# sheet_V1.net
KiCad netlist of a schematic drawn in Altium Designer
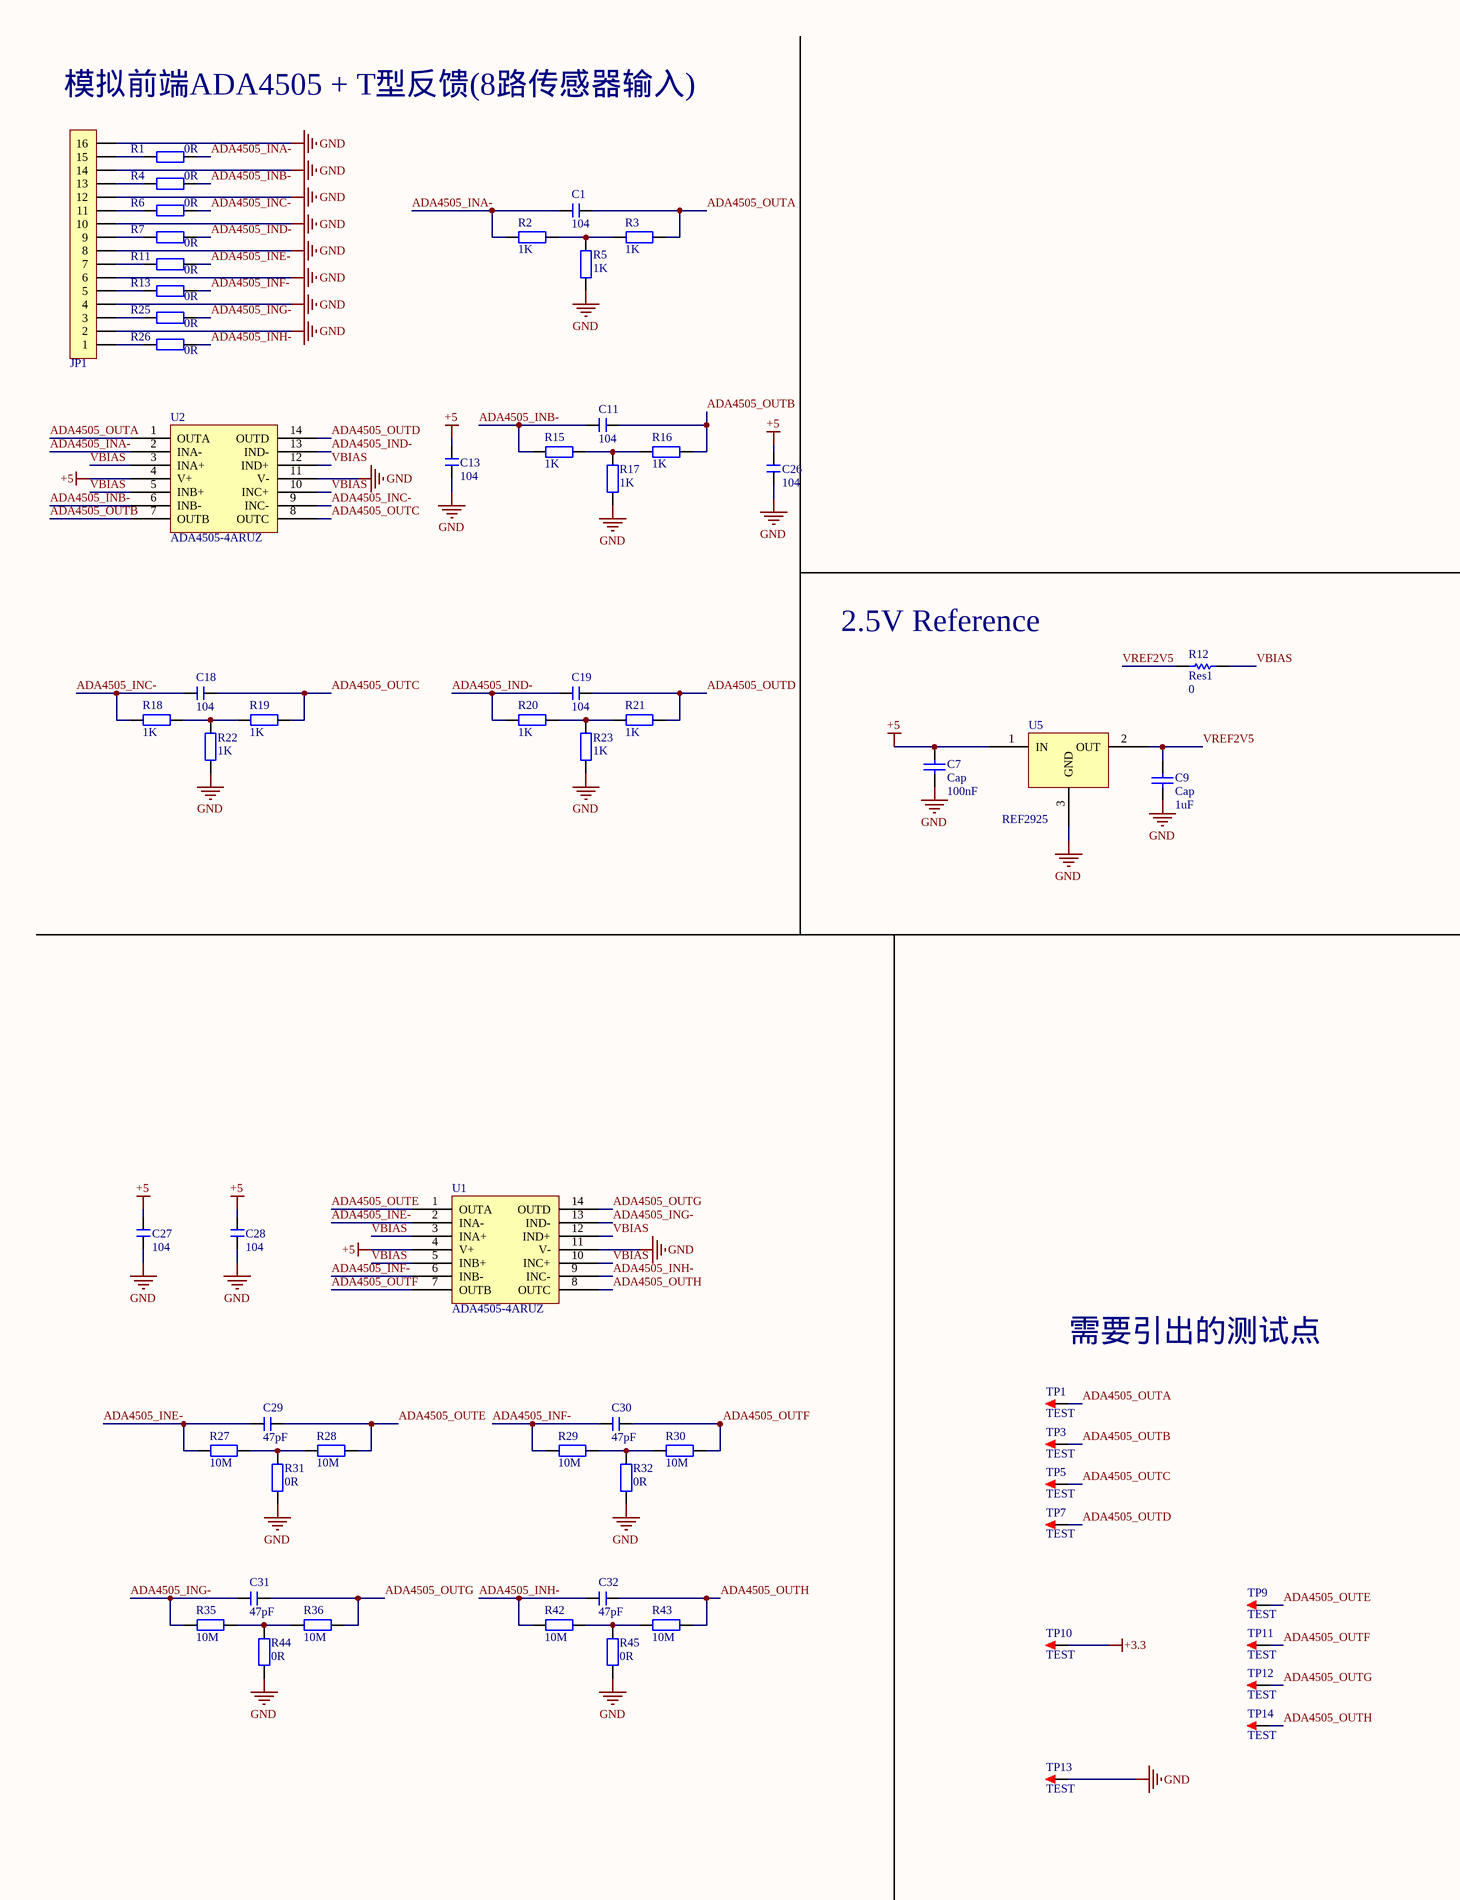
[diagram p0: sheet_V1.SchDoc, left]
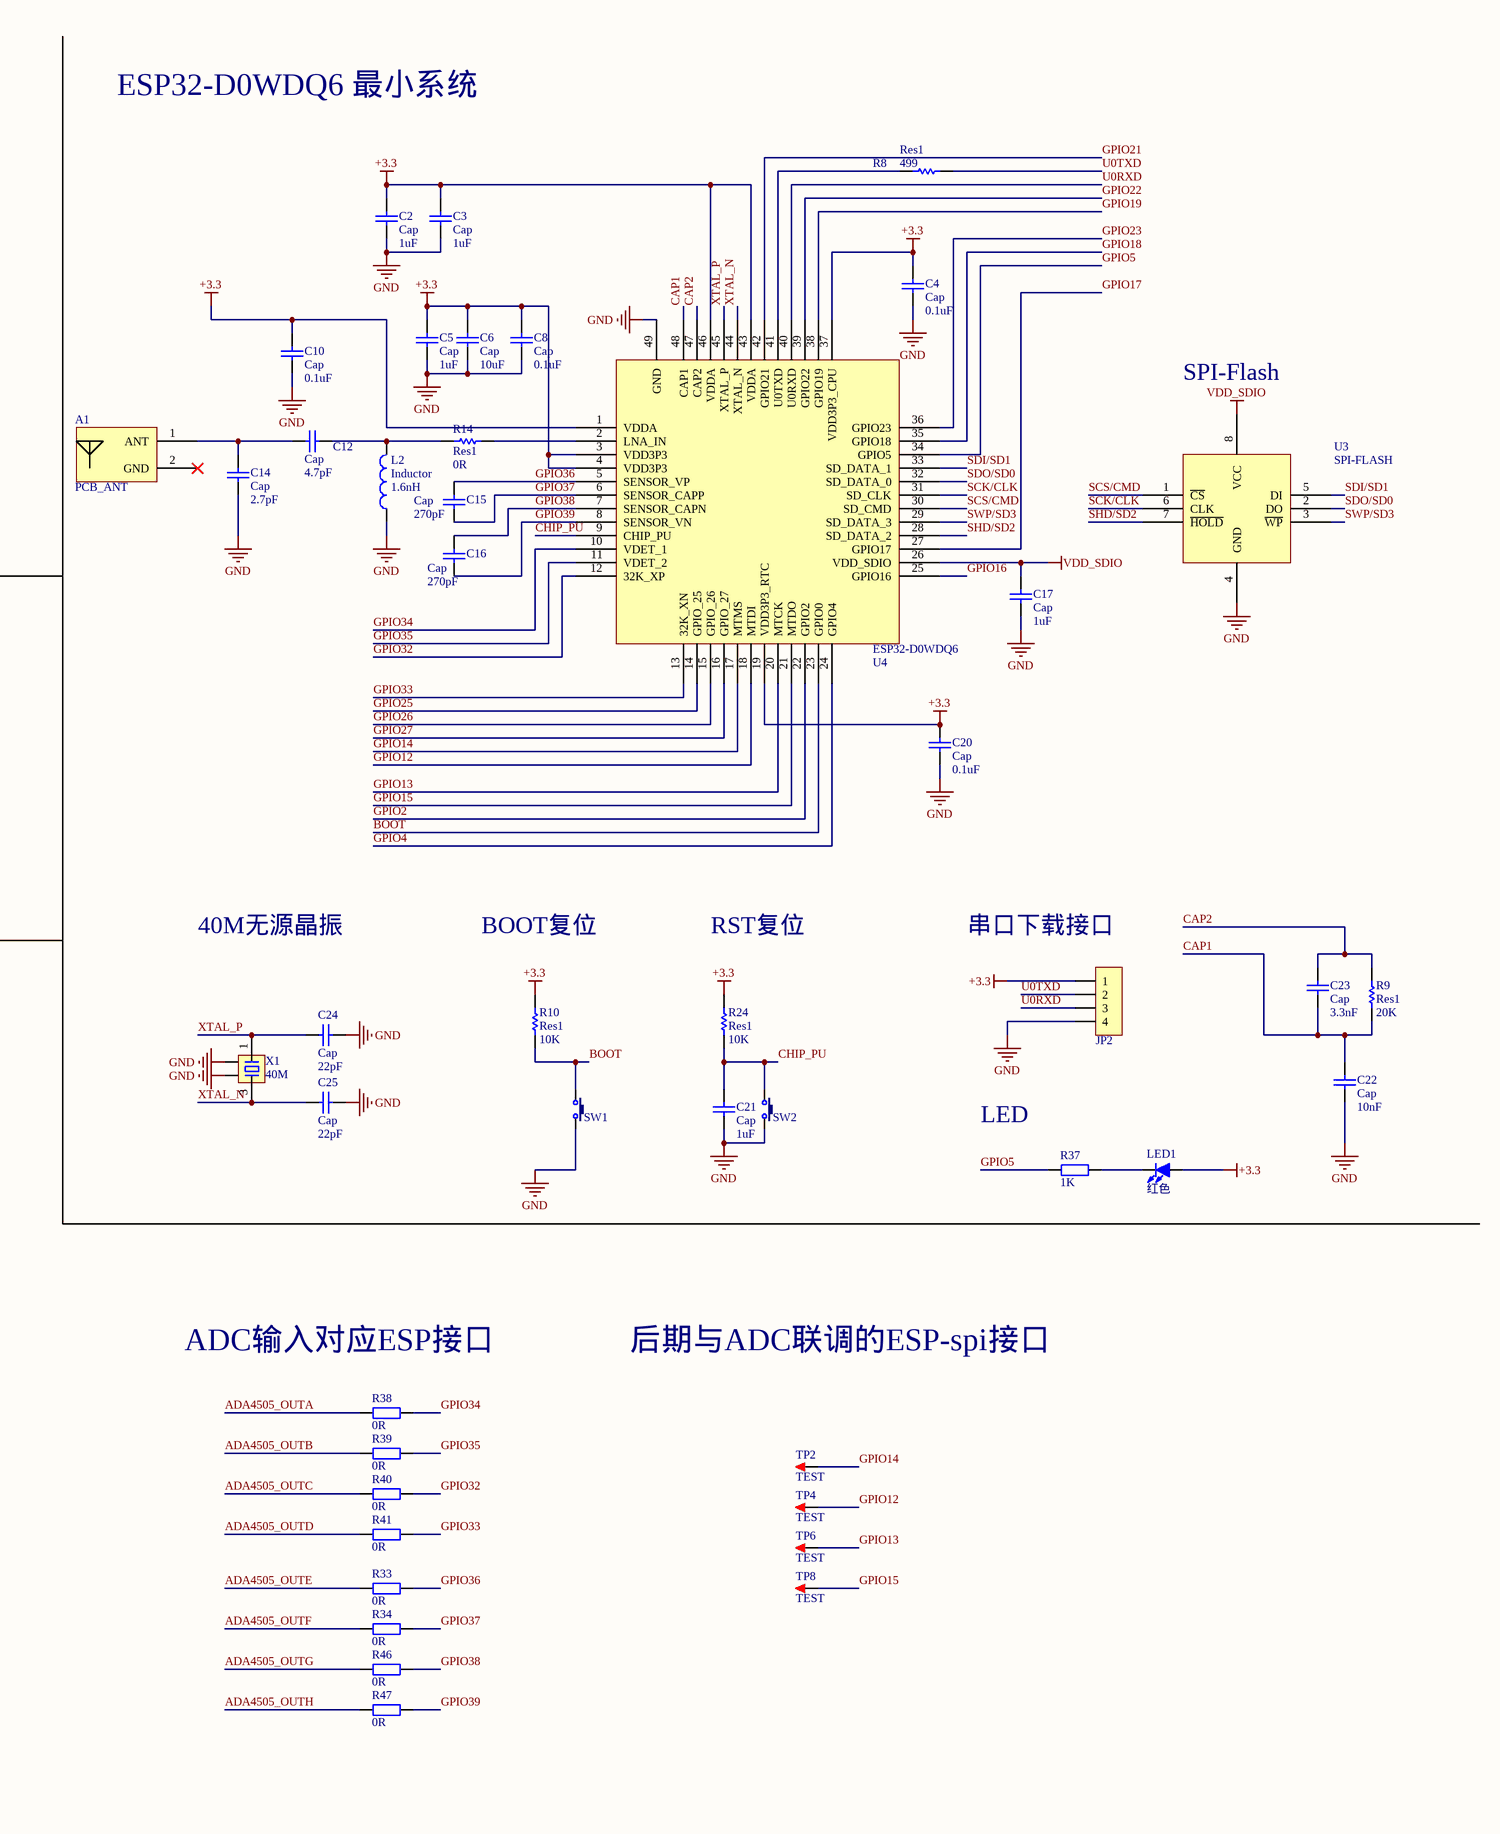
[diagram p1: sheet_V1.SchDoc, right]

(export (version "E")
  (design (tool "Eeschema 10.0.6"))
  (components
    (comp (ref "A1")
      (value "PCB_ANT")
      (footprint "PCB_ANT")
      (description "2.4G-esp32")
      (libsource (lib "Schlib1") (part "PCB_ANT"))
    )
    (comp (ref "C1")
      (value "104")
      (footprint "C 0402_L")
      (description "无极性贴片电容")
      (fields (field (name "版权归属") "源创客"))
      (libsource (lib "Basic_Integrated_Library") (part "C"))
    )
    (comp (ref "C2")
      (value "Cap")
      (footprint "C 0402_L")
      (description "Capacitor")
      (fields (field (name "ALTIUM_VALUE") "1uF") (field (name "PUBLISHER") "Altium Limited"))
      (libsource (lib "Miscellaneous Devices") (part "Cap"))
    )
    (comp (ref "C3")
      (value "Cap")
      (footprint "C 0402_L")
      (description "Capacitor")
      (fields (field (name "ALTIUM_VALUE") "1uF") (field (name "PUBLISHER") "Altium Limited"))
      (libsource (lib "Miscellaneous Devices") (part "Cap"))
    )
    (comp (ref "C4")
      (value "Cap")
      (footprint "C 0402_L")
      (description "Capacitor")
      (fields (field (name "ALTIUM_VALUE") "0.1uF") (field (name "PUBLISHER") "Altium Limited"))
      (libsource (lib "Miscellaneous Devices") (part "Cap"))
    )
    (comp (ref "C5")
      (value "Cap")
      (footprint "C 0402_L")
      (description "Capacitor")
      (fields (field (name "ALTIUM_VALUE") "1uF") (field (name "PUBLISHER") "Altium Limited"))
      (libsource (lib "Miscellaneous Devices") (part "Cap"))
    )
    (comp (ref "C6")
      (value "Cap")
      (footprint "C 0402_L")
      (description "Capacitor")
      (fields (field (name "ALTIUM_VALUE") "10uF") (field (name "PUBLISHER") "Altium Limited"))
      (libsource (lib "Miscellaneous Devices") (part "Cap"))
    )
    (comp (ref "C7")
      (value "Cap")
      (footprint "C 0402_L")
      (description "Capacitor")
      (fields (field (name "ALTIUM_VALUE") "100nF") (field (name "PUBLISHER") "Altium Limited"))
      (libsource (lib "Miscellaneous Devices") (part "Cap"))
    )
    (comp (ref "C8")
      (value "Cap")
      (footprint "C 0402_L")
      (description "Capacitor")
      (fields (field (name "ALTIUM_VALUE") "0.1uF") (field (name "PUBLISHER") "Altium Limited"))
      (libsource (lib "Miscellaneous Devices") (part "Cap"))
    )
    (comp (ref "C9")
      (value "Cap")
      (footprint "C 0402_L")
      (description "Capacitor")
      (fields (field (name "ALTIUM_VALUE") "1uF") (field (name "PUBLISHER") "Altium Limited"))
      (libsource (lib "Miscellaneous Devices") (part "Cap"))
    )
    (comp (ref "C10")
      (value "Cap")
      (footprint "C 0402_L")
      (description "Capacitor")
      (fields (field (name "ALTIUM_VALUE") "0.1uF") (field (name "PUBLISHER") "Altium Limited"))
      (libsource (lib "Miscellaneous Devices") (part "Cap"))
    )
    (comp (ref "C11")
      (value "104")
      (footprint "C 0402_L")
      (description "无极性贴片电容")
      (fields (field (name "版权归属") "源创客"))
      (libsource (lib "Basic_Integrated_Library") (part "C"))
    )
    (comp (ref "C12")
      (value "Cap")
      (footprint "C 0402_L")
      (description "Capacitor")
      (fields (field (name "ALTIUM_VALUE") "4.7pF") (field (name "PUBLISHER") "Altium Limited"))
      (libsource (lib "Miscellaneous Devices") (part "Cap"))
    )
    (comp (ref "C13")
      (value "104")
      (footprint "C 0402_L")
      (description "无极性贴片电容")
      (fields (field (name "版权归属") "源创客"))
      (libsource (lib "Basic_Integrated_Library") (part "C"))
    )
    (comp (ref "C14")
      (value "Cap")
      (footprint "C 0402_L")
      (description "Capacitor")
      (fields (field (name "ALTIUM_VALUE") "2.7pF") (field (name "PUBLISHER") "Altium Limited"))
      (libsource (lib "Miscellaneous Devices") (part "Cap"))
    )
    (comp (ref "C15")
      (value "Cap")
      (footprint "C 0402_L")
      (description "Capacitor")
      (fields (field (name "ALTIUM_VALUE") "270pF") (field (name "PUBLISHER") "Altium Limited"))
      (libsource (lib "Miscellaneous Devices") (part "Cap"))
    )
    (comp (ref "C16")
      (value "Cap")
      (footprint "C 0402_L")
      (description "Capacitor")
      (fields (field (name "ALTIUM_VALUE") "270pF") (field (name "PUBLISHER") "Altium Limited"))
      (libsource (lib "Miscellaneous Devices") (part "Cap"))
    )
    (comp (ref "C17")
      (value "Cap")
      (footprint "C 0402_L")
      (description "Capacitor")
      (fields (field (name "ALTIUM_VALUE") "1uF") (field (name "PUBLISHER") "Altium Limited"))
      (libsource (lib "Miscellaneous Devices") (part "Cap"))
    )
    (comp (ref "C18")
      (value "104")
      (footprint "C 0402_L")
      (description "无极性贴片电容")
      (fields (field (name "版权归属") "源创客"))
      (libsource (lib "Basic_Integrated_Library") (part "C"))
    )
    (comp (ref "C19")
      (value "104")
      (footprint "C 0402_L")
      (description "无极性贴片电容")
      (fields (field (name "版权归属") "源创客"))
      (libsource (lib "Basic_Integrated_Library") (part "C"))
    )
    (comp (ref "C20")
      (value "Cap")
      (footprint "C 0402_L")
      (description "Capacitor")
      (fields (field (name "ALTIUM_VALUE") "0.1uF") (field (name "PUBLISHER") "Altium Limited"))
      (libsource (lib "Miscellaneous Devices") (part "Cap"))
    )
    (comp (ref "C21")
      (value "Cap")
      (footprint "C 0402_L")
      (description "Capacitor")
      (fields (field (name "ALTIUM_VALUE") "1uF") (field (name "PUBLISHER") "Altium Limited"))
      (libsource (lib "Miscellaneous Devices") (part "Cap"))
    )
    (comp (ref "C22")
      (value "Cap")
      (footprint "C 0402_L")
      (description "Capacitor")
      (fields (field (name "ALTIUM_VALUE") "10nF") (field (name "PUBLISHER") "Altium Limited"))
      (libsource (lib "Miscellaneous Devices") (part "Cap"))
    )
    (comp (ref "C23")
      (value "Cap")
      (footprint "C 0402_L")
      (description "Capacitor")
      (fields (field (name "ALTIUM_VALUE") "3.3nF") (field (name "PUBLISHER") "Altium Limited"))
      (libsource (lib "Miscellaneous Devices") (part "Cap"))
    )
    (comp (ref "C24")
      (value "Cap")
      (footprint "C 0402_L")
      (description "Capacitor")
      (fields (field (name "ALTIUM_VALUE") "22pF") (field (name "PUBLISHER") "Altium Limited"))
      (libsource (lib "Miscellaneous Devices") (part "Cap"))
    )
    (comp (ref "C25")
      (value "Cap")
      (footprint "C 0402_L")
      (description "Capacitor")
      (fields (field (name "ALTIUM_VALUE") "22pF") (field (name "PUBLISHER") "Altium Limited"))
      (libsource (lib "Miscellaneous Devices") (part "Cap"))
    )
    (comp (ref "C26")
      (value "104")
      (footprint "C 0402_L")
      (description "无极性贴片电容")
      (fields (field (name "版权归属") "源创客"))
      (libsource (lib "Basic_Integrated_Library") (part "C"))
    )
    (comp (ref "C27")
      (value "104")
      (footprint "C 0402_L")
      (description "无极性贴片电容")
      (fields (field (name "版权归属") "源创客"))
      (libsource (lib "Basic_Integrated_Library") (part "C"))
    )
    (comp (ref "C28")
      (value "104")
      (footprint "C 0402_L")
      (description "无极性贴片电容")
      (fields (field (name "版权归属") "源创客"))
      (libsource (lib "Basic_Integrated_Library") (part "C"))
    )
    (comp (ref "C29")
      (value "47pF")
      (footprint "C 0402_L")
      (description "无极性贴片电容")
      (fields (field (name "版权归属") "源创客"))
      (libsource (lib "Basic_Integrated_Library") (part "C"))
    )
    (comp (ref "C30")
      (value "47pF")
      (footprint "C 0402_L")
      (description "无极性贴片电容")
      (fields (field (name "版权归属") "源创客"))
      (libsource (lib "Basic_Integrated_Library") (part "C"))
    )
    (comp (ref "C31")
      (value "47pF")
      (footprint "C 0402_L")
      (description "无极性贴片电容")
      (fields (field (name "版权归属") "源创客"))
      (libsource (lib "Basic_Integrated_Library") (part "C"))
    )
    (comp (ref "C32")
      (value "47pF")
      (footprint "C 0402_L")
      (description "无极性贴片电容")
      (fields (field (name "版权归属") "源创客"))
      (libsource (lib "Basic_Integrated_Library") (part "C"))
    )
    (comp (ref "JP1")
      (value "HDR-1X16")
      (footprint "FPC0.5 2H-WS-16P")
      (description "16P接插件")
      (fields (field (name "版权归属") "源创客"))
      (libsource (lib "Basic_Integrated_Library") (part "Header 16"))
    )
    (comp (ref "JP2")
      (value "HDR-1X4")
      (footprint "2.54_pad_4")
      (description "4P接插件")
      (fields (field (name "版权归属") "源创客"))
      (libsource (lib "Basic_Integrated_Library") (part "Header 4"))
    )
    (comp (ref "L2")
      (value "Inductor")
      (footprint "L 0402")
      (fields (field (name "ALTIUM_VALUE") "1.6nH") (field (name "PUBLISHER") "Altium Limited"))
      (libsource (lib "Miscellaneous Devices") (part "Inductor"))
    )
    (comp (ref "LED1")
      (value "红色")
      (footprint "LED 0603R")
      (description "贴片LED")
      (fields (field (name "版权归属") "源创客"))
      (libsource (lib "Basic_Integrated_Library") (part "LED-SMD"))
    )
    (comp (ref "R1")
      (value "0R")
      (footprint "R 0402_L")
      (description "贴片电阻")
      (fields (field (name "版权归属") "源创客"))
      (libsource (lib "Basic_Integrated_Library") (part "R"))
    )
    (comp (ref "R2")
      (value "1K")
      (footprint "R 0805_L")
      (description "贴片电阻")
      (fields (field (name "版权归属") "源创客"))
      (libsource (lib "Basic_Integrated_Library") (part "R"))
    )
    (comp (ref "R3")
      (value "1K")
      (footprint "R 0805_L")
      (description "贴片电阻")
      (fields (field (name "版权归属") "源创客"))
      (libsource (lib "Basic_Integrated_Library") (part "R"))
    )
    (comp (ref "R4")
      (value "0R")
      (footprint "R 0402_L")
      (description "贴片电阻")
      (fields (field (name "版权归属") "源创客"))
      (libsource (lib "Basic_Integrated_Library") (part "R"))
    )
    (comp (ref "R5")
      (value "1K")
      (footprint "R 0805_L")
      (description "贴片电阻")
      (fields (field (name "版权归属") "源创客"))
      (libsource (lib "Basic_Integrated_Library") (part "R"))
    )
    (comp (ref "R6")
      (value "0R")
      (footprint "R 0402_L")
      (description "贴片电阻")
      (fields (field (name "版权归属") "源创客"))
      (libsource (lib "Basic_Integrated_Library") (part "R"))
    )
    (comp (ref "R7")
      (value "0R")
      (footprint "R 0402_L")
      (description "贴片电阻")
      (fields (field (name "版权归属") "源创客"))
      (libsource (lib "Basic_Integrated_Library") (part "R"))
    )
    (comp (ref "R8")
      (value "Res1")
      (footprint "R 0402_L")
      (description "Resistor")
      (fields (field (name "ALTIUM_VALUE") "499") (field (name "PUBLISHER") "Altium Limited"))
      (libsource (lib "Miscellaneous Devices") (part "Res1"))
    )
    (comp (ref "R9")
      (value "Res1")
      (footprint "R 0402_L")
      (description "Resistor")
      (fields (field (name "ALTIUM_VALUE") "20K") (field (name "PUBLISHER") "Altium Limited"))
      (libsource (lib "Miscellaneous Devices") (part "Res1"))
    )
    (comp (ref "R10")
      (value "Res1")
      (footprint "R 0402_L")
      (description "Resistor")
      (fields (field (name "ALTIUM_VALUE") "10K") (field (name "PUBLISHER") "Altium Limited"))
      (libsource (lib "Miscellaneous Devices") (part "Res1"))
    )
    (comp (ref "R11")
      (value "0R")
      (footprint "R 0402_L")
      (description "贴片电阻")
      (fields (field (name "版权归属") "源创客"))
      (libsource (lib "Basic_Integrated_Library") (part "R"))
    )
    (comp (ref "R12")
      (value "Res1")
      (footprint "R 0402_L")
      (description "Resistor")
      (fields (field (name "ALTIUM_VALUE") "0") (field (name "PUBLISHER") "Altium Limited"))
      (libsource (lib "Miscellaneous Devices") (part "Res1"))
    )
    (comp (ref "R13")
      (value "0R")
      (footprint "R 0402_L")
      (description "贴片电阻")
      (fields (field (name "版权归属") "源创客"))
      (libsource (lib "Basic_Integrated_Library") (part "R"))
    )
    (comp (ref "R14")
      (value "Res1")
      (footprint "R 0402_L")
      (description "Resistor")
      (fields (field (name "ALTIUM_VALUE") "0R") (field (name "PUBLISHER") "Altium Limited"))
      (libsource (lib "Miscellaneous Devices") (part "Res1"))
    )
    (comp (ref "R15")
      (value "1K")
      (footprint "R 0805_L")
      (description "贴片电阻")
      (fields (field (name "版权归属") "源创客"))
      (libsource (lib "Basic_Integrated_Library") (part "R"))
    )
    (comp (ref "R16")
      (value "1K")
      (footprint "R 0805_L")
      (description "贴片电阻")
      (fields (field (name "版权归属") "源创客"))
      (libsource (lib "Basic_Integrated_Library") (part "R"))
    )
    (comp (ref "R17")
      (value "1K")
      (footprint "R 0805_L")
      (description "贴片电阻")
      (fields (field (name "版权归属") "源创客"))
      (libsource (lib "Basic_Integrated_Library") (part "R"))
    )
    (comp (ref "R18")
      (value "1K")
      (footprint "R 0805_L")
      (description "贴片电阻")
      (fields (field (name "版权归属") "源创客"))
      (libsource (lib "Basic_Integrated_Library") (part "R"))
    )
    (comp (ref "R19")
      (value "1K")
      (footprint "R 0805_L")
      (description "贴片电阻")
      (fields (field (name "版权归属") "源创客"))
      (libsource (lib "Basic_Integrated_Library") (part "R"))
    )
    (comp (ref "R20")
      (value "1K")
      (footprint "R 0805_L")
      (description "贴片电阻")
      (fields (field (name "版权归属") "源创客"))
      (libsource (lib "Basic_Integrated_Library") (part "R"))
    )
    (comp (ref "R21")
      (value "1K")
      (footprint "R 0805_L")
      (description "贴片电阻")
      (fields (field (name "版权归属") "源创客"))
      (libsource (lib "Basic_Integrated_Library") (part "R"))
    )
    (comp (ref "R22")
      (value "1K")
      (footprint "R 0805_L")
      (description "贴片电阻")
      (fields (field (name "版权归属") "源创客"))
      (libsource (lib "Basic_Integrated_Library") (part "R"))
    )
    (comp (ref "R23")
      (value "1K")
      (footprint "R 0805_L")
      (description "贴片电阻")
      (fields (field (name "版权归属") "源创客"))
      (libsource (lib "Basic_Integrated_Library") (part "R"))
    )
    (comp (ref "R24")
      (value "Res1")
      (footprint "R 0402_L")
      (description "Resistor")
      (fields (field (name "ALTIUM_VALUE") "10K") (field (name "PUBLISHER") "Altium Limited"))
      (libsource (lib "Miscellaneous Devices") (part "Res1"))
    )
    (comp (ref "R25")
      (value "0R")
      (footprint "R 0402_L")
      (description "贴片电阻")
      (fields (field (name "版权归属") "源创客"))
      (libsource (lib "Basic_Integrated_Library") (part "R"))
    )
    (comp (ref "R26")
      (value "0R")
      (footprint "R 0402_L")
      (description "贴片电阻")
      (fields (field (name "版权归属") "源创客"))
      (libsource (lib "Basic_Integrated_Library") (part "R"))
    )
    (comp (ref "R27")
      (value "10M")
      (footprint "R 0805_L")
      (description "贴片电阻")
      (fields (field (name "版权归属") "源创客"))
      (libsource (lib "Basic_Integrated_Library") (part "R"))
    )
    (comp (ref "R28")
      (value "10M")
      (footprint "R 0805_L")
      (description "贴片电阻")
      (fields (field (name "版权归属") "源创客"))
      (libsource (lib "Basic_Integrated_Library") (part "R"))
    )
    (comp (ref "R29")
      (value "10M")
      (footprint "R 0805_L")
      (description "贴片电阻")
      (fields (field (name "版权归属") "源创客"))
      (libsource (lib "Basic_Integrated_Library") (part "R"))
    )
    (comp (ref "R30")
      (value "10M")
      (footprint "R 0805_L")
      (description "贴片电阻")
      (fields (field (name "版权归属") "源创客"))
      (libsource (lib "Basic_Integrated_Library") (part "R"))
    )
    (comp (ref "R31")
      (value "0R")
      (footprint "R 0805_L")
      (description "贴片电阻")
      (fields (field (name "版权归属") "源创客"))
      (libsource (lib "Basic_Integrated_Library") (part "R"))
    )
    (comp (ref "R32")
      (value "0R")
      (footprint "R 0805_L")
      (description "贴片电阻")
      (fields (field (name "版权归属") "源创客"))
      (libsource (lib "Basic_Integrated_Library") (part "R"))
    )
    (comp (ref "R33")
      (value "0R")
      (footprint "R 0402_L")
      (description "贴片电阻")
      (fields (field (name "版权归属") "源创客"))
      (libsource (lib "Basic_Integrated_Library") (part "R"))
    )
    (comp (ref "R34")
      (value "0R")
      (footprint "R 0402_L")
      (description "贴片电阻")
      (fields (field (name "版权归属") "源创客"))
      (libsource (lib "Basic_Integrated_Library") (part "R"))
    )
    (comp (ref "R35")
      (value "10M")
      (footprint "R 0805_L")
      (description "贴片电阻")
      (fields (field (name "版权归属") "源创客"))
      (libsource (lib "Basic_Integrated_Library") (part "R"))
    )
    (comp (ref "R36")
      (value "10M")
      (footprint "R 0805_L")
      (description "贴片电阻")
      (fields (field (name "版权归属") "源创客"))
      (libsource (lib "Basic_Integrated_Library") (part "R"))
    )
    (comp (ref "R37")
      (value "1K")
      (footprint "R 0402_L")
      (description "贴片电阻")
      (fields (field (name "版权归属") "源创客"))
      (libsource (lib "Basic_Integrated_Library") (part "R"))
    )
    (comp (ref "R38")
      (value "0R")
      (footprint "R 0402_L")
      (description "贴片电阻")
      (fields (field (name "版权归属") "源创客"))
      (libsource (lib "Basic_Integrated_Library") (part "R"))
    )
    (comp (ref "R39")
      (value "0R")
      (footprint "R 0402_L")
      (description "贴片电阻")
      (fields (field (name "版权归属") "源创客"))
      (libsource (lib "Basic_Integrated_Library") (part "R"))
    )
    (comp (ref "R40")
      (value "0R")
      (footprint "R 0402_L")
      (description "贴片电阻")
      (fields (field (name "版权归属") "源创客"))
      (libsource (lib "Basic_Integrated_Library") (part "R"))
    )
    (comp (ref "R41")
      (value "0R")
      (footprint "R 0402_L")
      (description "贴片电阻")
      (fields (field (name "版权归属") "源创客"))
      (libsource (lib "Basic_Integrated_Library") (part "R"))
    )
    (comp (ref "R42")
      (value "10M")
      (footprint "R 0805_L")
      (description "贴片电阻")
      (fields (field (name "版权归属") "源创客"))
      (libsource (lib "Basic_Integrated_Library") (part "R"))
    )
    (comp (ref "R43")
      (value "10M")
      (footprint "R 0805_L")
      (description "贴片电阻")
      (fields (field (name "版权归属") "源创客"))
      (libsource (lib "Basic_Integrated_Library") (part "R"))
    )
    (comp (ref "R44")
      (value "0R")
      (footprint "R 0805_L")
      (description "贴片电阻")
      (fields (field (name "版权归属") "源创客"))
      (libsource (lib "Basic_Integrated_Library") (part "R"))
    )
    (comp (ref "R45")
      (value "0R")
      (footprint "R 0805_L")
      (description "贴片电阻")
      (fields (field (name "版权归属") "源创客"))
      (libsource (lib "Basic_Integrated_Library") (part "R"))
    )
    (comp (ref "R46")
      (value "0R")
      (footprint "R 0402_L")
      (description "贴片电阻")
      (fields (field (name "版权归属") "源创客"))
      (libsource (lib "Basic_Integrated_Library") (part "R"))
    )
    (comp (ref "R47")
      (value "0R")
      (footprint "R 0402_L")
      (description "贴片电阻")
      (fields (field (name "版权归属") "源创客"))
      (libsource (lib "Basic_Integrated_Library") (part "R"))
    )
    (comp (ref "SW1")
      (value "3x6x5")
      (footprint "KEY-little")
      (description "3x6轻触开关")
      (fields (field (name "版权归属") "源创客"))
      (libsource (lib "5.1   - 按键-开关") (part "TSW 3x6"))
    )
    (comp (ref "SW2")
      (value "3x6x5")
      (footprint "KEY-little")
      (description "3x6轻触开关")
      (fields (field (name "版权归属") "源创客"))
      (libsource (lib "5.1   - 按键-开关") (part "TSW 3x6"))
    )
    (comp (ref "TP1")
      (value "TEST")
      (footprint "TEST 0.8")
      (description "测试点")
      (fields (field (name "版权归属") "源创客"))
      (libsource (lib "Basic_Integrated_Library") (part "TEST"))
    )
    (comp (ref "TP2")
      (value "TEST")
      (footprint "TEST 0.8")
      (description "测试点")
      (fields (field (name "版权归属") "源创客"))
      (libsource (lib "Basic_Integrated_Library") (part "TEST"))
    )
    (comp (ref "TP3")
      (value "TEST")
      (footprint "TEST 0.8")
      (description "测试点")
      (fields (field (name "版权归属") "源创客"))
      (libsource (lib "Basic_Integrated_Library") (part "TEST"))
    )
    (comp (ref "TP4")
      (value "TEST")
      (footprint "TEST 0.8")
      (description "测试点")
      (fields (field (name "版权归属") "源创客"))
      (libsource (lib "Basic_Integrated_Library") (part "TEST"))
    )
    (comp (ref "TP5")
      (value "TEST")
      (footprint "TEST 0.8")
      (description "测试点")
      (fields (field (name "版权归属") "源创客"))
      (libsource (lib "Basic_Integrated_Library") (part "TEST"))
    )
    (comp (ref "TP6")
      (value "TEST")
      (footprint "TEST 0.8")
      (description "测试点")
      (fields (field (name "版权归属") "源创客"))
      (libsource (lib "Basic_Integrated_Library") (part "TEST"))
    )
    (comp (ref "TP7")
      (value "TEST")
      (footprint "TEST 0.8")
      (description "测试点")
      (fields (field (name "版权归属") "源创客"))
      (libsource (lib "Basic_Integrated_Library") (part "TEST"))
    )
    (comp (ref "TP8")
      (value "TEST")
      (footprint "TEST 0.8")
      (description "测试点")
      (fields (field (name "版权归属") "源创客"))
      (libsource (lib "Basic_Integrated_Library") (part "TEST"))
    )
    (comp (ref "TP9")
      (value "TEST")
      (footprint "TEST 0.8")
      (description "测试点")
      (fields (field (name "版权归属") "源创客"))
      (libsource (lib "Basic_Integrated_Library") (part "TEST"))
    )
    (comp (ref "TP10")
      (value "TEST")
      (footprint "TEST 0.8")
      (description "测试点")
      (fields (field (name "版权归属") "源创客"))
      (libsource (lib "Basic_Integrated_Library") (part "TEST"))
    )
    (comp (ref "TP11")
      (value "TEST")
      (footprint "TEST 0.8")
      (description "测试点")
      (fields (field (name "版权归属") "源创客"))
      (libsource (lib "Basic_Integrated_Library") (part "TEST"))
    )
    (comp (ref "TP12")
      (value "TEST")
      (footprint "TEST 0.8")
      (description "测试点")
      (fields (field (name "版权归属") "源创客"))
      (libsource (lib "Basic_Integrated_Library") (part "TEST"))
    )
    (comp (ref "TP13")
      (value "TEST")
      (footprint "TEST 0.8")
      (description "测试点")
      (fields (field (name "版权归属") "源创客"))
      (libsource (lib "Basic_Integrated_Library") (part "TEST"))
    )
    (comp (ref "TP14")
      (value "TEST")
      (footprint "TEST 0.8")
      (description "测试点")
      (fields (field (name "版权归属") "源创客"))
      (libsource (lib "Basic_Integrated_Library") (part "TEST"))
    )
    (comp (ref "U1")
      (value "ADA4505-4ARUZ")
      (footprint "ADA4505-4ARUZ")
      (libsource (lib "Schlib1") (part "ADA4505-4ARUZ"))
    )
    (comp (ref "U2")
      (value "ADA4505-4ARUZ")
      (footprint "ADA4505-4ARUZ")
      (libsource (lib "Schlib1") (part "ADA4505-4ARUZ"))
    )
    (comp (ref "U3")
      (value "SPI-FLASH")
      (footprint "SPI-Flash")
      (libsource (lib "Schlib1") (part "SPI-FLASH"))
    )
    (comp (ref "U4")
      (value "ESP32-D0WDQ6")
      (footprint "ESP32D0WDQ6")
      (libsource (lib "Schlib1") (part "ESP32-D0WDQ6"))
    )
    (comp (ref "U5")
      (value "REF2925")
      (footprint "REF2925AIDBZR")
      (description "2.5V reference")
      (libsource (lib "Schlib1") (part "REF2925"))
    )
    (comp (ref "X1")
      (value "40M")
      (footprint "晶振3225")
      (description "4脚无源晶振")
      (fields (field (name "版权归属") "源创客"))
      (libsource (lib "晶体振荡器") (part "XTAL-4P"))
    )
  )
  (nets
    (net (code "1") (name "+3.3") (class "Default")
      (node (ref "C10") (pin "2") (pinfunction "2_2") (pintype "passive"))
      (node (ref "C2") (pin "2") (pinfunction "2_2") (pintype "passive"))
      (node (ref "C20") (pin "2") (pinfunction "2_2") (pintype "passive"))
      (node (ref "C3") (pin "2") (pinfunction "2_2") (pintype "passive"))
      (node (ref "C4") (pin "2") (pinfunction "2_2") (pintype "passive"))
      (node (ref "C5") (pin "2") (pinfunction "2_2") (pintype "passive"))
      (node (ref "C6") (pin "2") (pinfunction "2_2") (pintype "passive"))
      (node (ref "C8") (pin "2") (pinfunction "2_2") (pintype "passive"))
      (node (ref "JP2") (pin "1") (pinfunction "1_1") (pintype "passive"))
      (node (ref "LED1") (pin "1") (pinfunction "A_1") (pintype "passive"))
      (node (ref "R10") (pin "2") (pinfunction "2_2") (pintype "passive"))
      (node (ref "R24") (pin "2") (pinfunction "2_2") (pintype "passive"))
      (node (ref "TP10") (pin "1") (pinfunction "1_1") (pintype "passive"))
      (node (ref "U4") (pin "1") (pinfunction "VDDA_1") (pintype "passive"))
      (node (ref "U4") (pin "19") (pinfunction "VDD3P3_RTC_19") (pintype "passive"))
      (node (ref "U4") (pin "3") (pinfunction "VDD3P3_3") (pintype "passive"))
      (node (ref "U4") (pin "37") (pinfunction "VDD3P3_CPU_37") (pintype "passive"))
      (node (ref "U4") (pin "4") (pinfunction "VDD3P3_4") (pintype "passive"))
      (node (ref "U4") (pin "43") (pinfunction "VDDA_43") (pintype "passive"))
      (node (ref "U4") (pin "46") (pinfunction "VDDA_46") (pintype "passive"))
    )
    (net (code "2") (name "+5") (class "Default")
      (node (ref "C13") (pin "2") (pinfunction "2_2") (pintype "passive"))
      (node (ref "C26") (pin "2") (pinfunction "2_2") (pintype "passive"))
      (node (ref "C27") (pin "2") (pinfunction "2_2") (pintype "passive"))
      (node (ref "C28") (pin "2") (pinfunction "2_2") (pintype "passive"))
      (node (ref "C7") (pin "2") (pinfunction "2_2") (pintype "passive"))
      (node (ref "U1") (pin "4") (pinfunction "V+_4") (pintype "passive"))
      (node (ref "U2") (pin "4") (pinfunction "V+_4") (pintype "passive"))
      (node (ref "U5") (pin "1") (pinfunction "IN_1") (pintype "passive"))
    )
    (net (code "3") (name "/ADA4505_INA-") (class "Default")
      (node (ref "C1") (pin "1") (pinfunction "1_1") (pintype "passive"))
      (node (ref "R1") (pin "2") (pinfunction "2_2") (pintype "passive"))
      (node (ref "R2") (pin "2") (pinfunction "2_2") (pintype "passive"))
      (node (ref "U2") (pin "2") (pinfunction "INA-_2") (pintype "passive"))
    )
    (net (code "4") (name "/ADA4505_INB-") (class "Default")
      (node (ref "C11") (pin "1") (pinfunction "1_1") (pintype "passive"))
      (node (ref "R15") (pin "2") (pinfunction "2_2") (pintype "passive"))
      (node (ref "R4") (pin "2") (pinfunction "2_2") (pintype "passive"))
      (node (ref "U2") (pin "6") (pinfunction "INB-_6") (pintype "passive"))
    )
    (net (code "5") (name "/ADA4505_INC-") (class "Default")
      (node (ref "C18") (pin "1") (pinfunction "1_1") (pintype "passive"))
      (node (ref "R18") (pin "2") (pinfunction "2_2") (pintype "passive"))
      (node (ref "R6") (pin "2") (pinfunction "2_2") (pintype "passive"))
      (node (ref "U2") (pin "9") (pinfunction "INC-_9") (pintype "passive"))
    )
    (net (code "6") (name "/ADA4505_IND-") (class "Default")
      (node (ref "C19") (pin "1") (pinfunction "1_1") (pintype "passive"))
      (node (ref "R20") (pin "2") (pinfunction "2_2") (pintype "passive"))
      (node (ref "R7") (pin "2") (pinfunction "2_2") (pintype "passive"))
      (node (ref "U2") (pin "13") (pinfunction "IND-_13") (pintype "passive"))
    )
    (net (code "7") (name "/ADA4505_INE-") (class "Default")
      (node (ref "C29") (pin "1") (pinfunction "1_1") (pintype "passive"))
      (node (ref "R11") (pin "2") (pinfunction "2_2") (pintype "passive"))
      (node (ref "R27") (pin "2") (pinfunction "2_2") (pintype "passive"))
      (node (ref "U1") (pin "2") (pinfunction "INA-_2") (pintype "passive"))
    )
    (net (code "8") (name "/ADA4505_INF-") (class "Default")
      (node (ref "C30") (pin "1") (pinfunction "1_1") (pintype "passive"))
      (node (ref "R13") (pin "2") (pinfunction "2_2") (pintype "passive"))
      (node (ref "R29") (pin "2") (pinfunction "2_2") (pintype "passive"))
      (node (ref "U1") (pin "6") (pinfunction "INB-_6") (pintype "passive"))
    )
    (net (code "9") (name "/ADA4505_ING-") (class "Default")
      (node (ref "C31") (pin "1") (pinfunction "1_1") (pintype "passive"))
      (node (ref "R25") (pin "2") (pinfunction "2_2") (pintype "passive"))
      (node (ref "R35") (pin "2") (pinfunction "2_2") (pintype "passive"))
      (node (ref "U1") (pin "13") (pinfunction "IND-_13") (pintype "passive"))
    )
    (net (code "10") (name "/ADA4505_INH-") (class "Default")
      (node (ref "C32") (pin "1") (pinfunction "1_1") (pintype "passive"))
      (node (ref "R26") (pin "2") (pinfunction "2_2") (pintype "passive"))
      (node (ref "R42") (pin "2") (pinfunction "2_2") (pintype "passive"))
      (node (ref "U1") (pin "9") (pinfunction "INC-_9") (pintype "passive"))
    )
    (net (code "11") (name "/ADA4505_OUTA") (class "Default")
      (node (ref "C1") (pin "2") (pinfunction "2_2") (pintype "passive"))
      (node (ref "R3") (pin "1") (pinfunction "1_1") (pintype "passive"))
      (node (ref "R38") (pin "1") (pinfunction "1_1") (pintype "passive"))
      (node (ref "TP1") (pin "1") (pinfunction "1_1") (pintype "passive"))
      (node (ref "U2") (pin "1") (pinfunction "OUTA_1") (pintype "passive"))
    )
    (net (code "12") (name "/ADA4505_OUTB") (class "Default")
      (node (ref "C11") (pin "2") (pinfunction "2_2") (pintype "passive"))
      (node (ref "R16") (pin "1") (pinfunction "1_1") (pintype "passive"))
      (node (ref "R39") (pin "1") (pinfunction "1_1") (pintype "passive"))
      (node (ref "TP3") (pin "1") (pinfunction "1_1") (pintype "passive"))
      (node (ref "U2") (pin "7") (pinfunction "OUTB_7") (pintype "passive"))
    )
    (net (code "13") (name "/ADA4505_OUTC") (class "Default")
      (node (ref "C18") (pin "2") (pinfunction "2_2") (pintype "passive"))
      (node (ref "R19") (pin "1") (pinfunction "1_1") (pintype "passive"))
      (node (ref "R40") (pin "1") (pinfunction "1_1") (pintype "passive"))
      (node (ref "TP5") (pin "1") (pinfunction "1_1") (pintype "passive"))
      (node (ref "U2") (pin "8") (pinfunction "OUTC_8") (pintype "passive"))
    )
    (net (code "14") (name "/ADA4505_OUTD") (class "Default")
      (node (ref "C19") (pin "2") (pinfunction "2_2") (pintype "passive"))
      (node (ref "R21") (pin "1") (pinfunction "1_1") (pintype "passive"))
      (node (ref "R41") (pin "1") (pinfunction "1_1") (pintype "passive"))
      (node (ref "TP7") (pin "1") (pinfunction "1_1") (pintype "passive"))
      (node (ref "U2") (pin "14") (pinfunction "OUTD_14") (pintype "passive"))
    )
    (net (code "15") (name "/ADA4505_OUTE") (class "Default")
      (node (ref "C29") (pin "2") (pinfunction "2_2") (pintype "passive"))
      (node (ref "R28") (pin "1") (pinfunction "1_1") (pintype "passive"))
      (node (ref "R33") (pin "1") (pinfunction "1_1") (pintype "passive"))
      (node (ref "TP9") (pin "1") (pinfunction "1_1") (pintype "passive"))
      (node (ref "U1") (pin "1") (pinfunction "OUTA_1") (pintype "passive"))
    )
    (net (code "16") (name "/ADA4505_OUTF") (class "Default")
      (node (ref "C30") (pin "2") (pinfunction "2_2") (pintype "passive"))
      (node (ref "R30") (pin "1") (pinfunction "1_1") (pintype "passive"))
      (node (ref "R34") (pin "1") (pinfunction "1_1") (pintype "passive"))
      (node (ref "TP11") (pin "1") (pinfunction "1_1") (pintype "passive"))
      (node (ref "U1") (pin "7") (pinfunction "OUTB_7") (pintype "passive"))
    )
    (net (code "17") (name "/ADA4505_OUTG") (class "Default")
      (node (ref "C31") (pin "2") (pinfunction "2_2") (pintype "passive"))
      (node (ref "R36") (pin "1") (pinfunction "1_1") (pintype "passive"))
      (node (ref "R46") (pin "1") (pinfunction "1_1") (pintype "passive"))
      (node (ref "TP12") (pin "1") (pinfunction "1_1") (pintype "passive"))
      (node (ref "U1") (pin "14") (pinfunction "OUTD_14") (pintype "passive"))
    )
    (net (code "18") (name "/ADA4505_OUTH") (class "Default")
      (node (ref "C32") (pin "2") (pinfunction "2_2") (pintype "passive"))
      (node (ref "R43") (pin "1") (pinfunction "1_1") (pintype "passive"))
      (node (ref "R47") (pin "1") (pinfunction "1_1") (pintype "passive"))
      (node (ref "TP14") (pin "1") (pinfunction "1_1") (pintype "passive"))
      (node (ref "U1") (pin "8") (pinfunction "OUTC_8") (pintype "passive"))
    )
    (net (code "19") (name "/BOOT") (class "Default")
      (node (ref "R10") (pin "1") (pinfunction "1_1") (pintype "passive"))
      (node (ref "SW1") (pin "1") (pinfunction "1_1") (pintype "passive"))
      (node (ref "U4") (pin "23") (pinfunction "GPIO0_23") (pintype "passive"))
    )
    (net (code "20") (name "/CAP1") (class "Default")
      (node (ref "C22") (pin "2") (pinfunction "2_2") (pintype "passive"))
      (node (ref "C23") (pin "1") (pinfunction "1_1") (pintype "passive"))
      (node (ref "R9") (pin "1") (pinfunction "1_1") (pintype "passive"))
      (node (ref "U4") (pin "48") (pinfunction "CAP1_48") (pintype "passive"))
    )
    (net (code "21") (name "/CAP2") (class "Default")
      (node (ref "C23") (pin "2") (pinfunction "2_2") (pintype "passive"))
      (node (ref "R9") (pin "2") (pinfunction "2_2") (pintype "passive"))
      (node (ref "U4") (pin "47") (pinfunction "CAP2_47") (pintype "passive"))
    )
    (net (code "22") (name "/CHIP_PU") (class "Default")
      (node (ref "C21") (pin "2") (pinfunction "2_2") (pintype "passive"))
      (node (ref "R24") (pin "1") (pinfunction "1_1") (pintype "passive"))
      (node (ref "SW2") (pin "1") (pinfunction "1_1") (pintype "passive"))
      (node (ref "U4") (pin "9") (pinfunction "CHIP_PU_9") (pintype "passive"))
    )
    (net (code "23") (name "/GPIO2") (class "Default")
      (node (ref "U4") (pin "22") (pinfunction "GPIO2_22") (pintype "passive"))
    )
    (net (code "24") (name "/GPIO4") (class "Default")
      (node (ref "U4") (pin "24") (pinfunction "GPIO4_24") (pintype "passive"))
    )
    (net (code "25") (name "/GPIO5") (class "Default")
      (node (ref "R37") (pin "1") (pinfunction "1_1") (pintype "passive"))
      (node (ref "U4") (pin "34") (pinfunction "GPIO5_34") (pintype "passive"))
    )
    (net (code "26") (name "/GPIO12") (class "Default")
      (node (ref "TP4") (pin "1") (pinfunction "1_1") (pintype "passive"))
      (node (ref "U4") (pin "18") (pinfunction "MTDI_18") (pintype "passive"))
    )
    (net (code "27") (name "/GPIO13") (class "Default")
      (node (ref "TP6") (pin "1") (pinfunction "1_1") (pintype "passive"))
      (node (ref "U4") (pin "20") (pinfunction "MTCK_20") (pintype "passive"))
    )
    (net (code "28") (name "/GPIO14") (class "Default")
      (node (ref "TP2") (pin "1") (pinfunction "1_1") (pintype "passive"))
      (node (ref "U4") (pin "17") (pinfunction "MTMS_17") (pintype "passive"))
    )
    (net (code "29") (name "/GPIO15") (class "Default")
      (node (ref "TP8") (pin "1") (pinfunction "1_1") (pintype "passive"))
      (node (ref "U4") (pin "21") (pinfunction "MTDO_21") (pintype "passive"))
    )
    (net (code "30") (name "/GPIO16") (class "Default")
      (node (ref "U4") (pin "25") (pinfunction "GPIO16_25") (pintype "passive"))
    )
    (net (code "31") (name "/GPIO17") (class "Default")
      (node (ref "U4") (pin "27") (pinfunction "GPIO17_27") (pintype "passive"))
    )
    (net (code "32") (name "/GPIO18") (class "Default")
      (node (ref "U4") (pin "35") (pinfunction "GPIO18_35") (pintype "passive"))
    )
    (net (code "33") (name "/GPIO19") (class "Default")
      (node (ref "U4") (pin "38") (pinfunction "GPIO19_38") (pintype "passive"))
    )
    (net (code "34") (name "/GPIO21") (class "Default")
      (node (ref "U4") (pin "42") (pinfunction "GPIO21_42") (pintype "passive"))
    )
    (net (code "35") (name "/GPIO22") (class "Default")
      (node (ref "U4") (pin "39") (pinfunction "GPIO22_39") (pintype "passive"))
    )
    (net (code "36") (name "/GPIO23") (class "Default")
      (node (ref "U4") (pin "36") (pinfunction "GPIO23_36") (pintype "passive"))
    )
    (net (code "37") (name "/GPIO25") (class "Default")
      (node (ref "U4") (pin "14") (pinfunction "GPIO_25_14") (pintype "passive"))
    )
    (net (code "38") (name "/GPIO26") (class "Default")
      (node (ref "U4") (pin "15") (pinfunction "GPIO_26_15") (pintype "passive"))
    )
    (net (code "39") (name "/GPIO27") (class "Default")
      (node (ref "U4") (pin "16") (pinfunction "GPIO_27_16") (pintype "passive"))
    )
    (net (code "40") (name "/GPIO32") (class "Default")
      (node (ref "R40") (pin "2") (pinfunction "2_2") (pintype "passive"))
      (node (ref "U4") (pin "12") (pinfunction "32K_XP_12") (pintype "passive"))
    )
    (net (code "41") (name "/GPIO33") (class "Default")
      (node (ref "R41") (pin "2") (pinfunction "2_2") (pintype "passive"))
      (node (ref "U4") (pin "13") (pinfunction "32K_XN_13") (pintype "passive"))
    )
    (net (code "42") (name "/GPIO34") (class "Default")
      (node (ref "R38") (pin "2") (pinfunction "2_2") (pintype "passive"))
      (node (ref "U4") (pin "10") (pinfunction "VDET_1_10") (pintype "passive"))
    )
    (net (code "43") (name "/GPIO35") (class "Default")
      (node (ref "R39") (pin "2") (pinfunction "2_2") (pintype "passive"))
      (node (ref "U4") (pin "11") (pinfunction "VDET_2_11") (pintype "passive"))
    )
    (net (code "44") (name "/GPIO36") (class "Default")
      (node (ref "C15") (pin "2") (pinfunction "2_2") (pintype "passive"))
      (node (ref "R33") (pin "2") (pinfunction "2_2") (pintype "passive"))
      (node (ref "U4") (pin "5") (pinfunction "SENSOR_VP_5") (pintype "passive"))
    )
    (net (code "45") (name "/GPIO37") (class "Default")
      (node (ref "C15") (pin "1") (pinfunction "1_1") (pintype "passive"))
      (node (ref "R34") (pin "2") (pinfunction "2_2") (pintype "passive"))
      (node (ref "U4") (pin "6") (pinfunction "SENSOR_CAPP_6") (pintype "passive"))
    )
    (net (code "46") (name "/GPIO38") (class "Default")
      (node (ref "C16") (pin "2") (pinfunction "2_2") (pintype "passive"))
      (node (ref "R46") (pin "2") (pinfunction "2_2") (pintype "passive"))
      (node (ref "U4") (pin "7") (pinfunction "SENSOR_CAPN_7") (pintype "passive"))
    )
    (net (code "47") (name "/GPIO39") (class "Default")
      (node (ref "C16") (pin "1") (pinfunction "1_1") (pintype "passive"))
      (node (ref "R47") (pin "2") (pinfunction "2_2") (pintype "passive"))
      (node (ref "U4") (pin "8") (pinfunction "SENSOR_VN_8") (pintype "passive"))
    )
    (net (code "48") (name "/SCK{slash}CLK") (class "Default")
      (node (ref "U3") (pin "6") (pinfunction "CLK_6") (pintype "passive"))
      (node (ref "U4") (pin "31") (pinfunction "SD_CLK_31") (pintype "passive"))
    )
    (net (code "49") (name "/SCS{slash}CMD") (class "Default")
      (node (ref "U3") (pin "1") (pinfunction "~{CS}_1") (pintype "passive"))
      (node (ref "U4") (pin "30") (pinfunction "SD_CMD_30") (pintype "passive"))
    )
    (net (code "50") (name "/SDI{slash}SD1") (class "Default")
      (node (ref "U3") (pin "5") (pinfunction "DI_5") (pintype "passive"))
      (node (ref "U4") (pin "33") (pinfunction "SD_DATA_1_33") (pintype "passive"))
    )
    (net (code "51") (name "/SDO{slash}SD0") (class "Default")
      (node (ref "U3") (pin "2") (pinfunction "DO_2") (pintype "passive"))
      (node (ref "U4") (pin "32") (pinfunction "SD_DATA_0_32") (pintype "passive"))
    )
    (net (code "52") (name "/SHD{slash}SD2") (class "Default")
      (node (ref "U3") (pin "7") (pinfunction "~{HOLD}_7") (pintype "passive"))
      (node (ref "U4") (pin "28") (pinfunction "SD_DATA_2_28") (pintype "passive"))
    )
    (net (code "53") (name "/SWP{slash}SD3") (class "Default")
      (node (ref "U3") (pin "3") (pinfunction "~{WP}_3") (pintype "passive"))
      (node (ref "U4") (pin "29") (pinfunction "SD_DATA_3_29") (pintype "passive"))
    )
    (net (code "54") (name "/U0RXD") (class "Default")
      (node (ref "JP2") (pin "3") (pinfunction "3_3") (pintype "passive"))
      (node (ref "U4") (pin "40") (pinfunction "U0RXD_40") (pintype "passive"))
    )
    (net (code "55") (name "/U0TXD") (class "Default")
      (node (ref "JP2") (pin "2") (pinfunction "2_2") (pintype "passive"))
      (node (ref "R8") (pin "2") (pinfunction "2_2") (pintype "passive"))
    )
    (net (code "56") (name "/VBIAS") (class "Default")
      (node (ref "R12") (pin "2") (pinfunction "2_2") (pintype "passive"))
      (node (ref "U1") (pin "10") (pinfunction "INC+_10") (pintype "passive"))
      (node (ref "U1") (pin "12") (pinfunction "IND+_12") (pintype "passive"))
      (node (ref "U1") (pin "3") (pinfunction "INA+_3") (pintype "passive"))
      (node (ref "U1") (pin "5") (pinfunction "INB+_5") (pintype "passive"))
      (node (ref "U2") (pin "10") (pinfunction "INC+_10") (pintype "passive"))
      (node (ref "U2") (pin "12") (pinfunction "IND+_12") (pintype "passive"))
      (node (ref "U2") (pin "3") (pinfunction "INA+_3") (pintype "passive"))
      (node (ref "U2") (pin "5") (pinfunction "INB+_5") (pintype "passive"))
    )
    (net (code "57") (name "/VREF2V5") (class "Default")
      (node (ref "C9") (pin "2") (pinfunction "2_2") (pintype "passive"))
      (node (ref "R12") (pin "1") (pinfunction "1_1") (pintype "passive"))
      (node (ref "U5") (pin "2") (pinfunction "OUT_2") (pintype "passive"))
    )
    (net (code "58") (name "/XTAL_N") (class "Default")
      (node (ref "C25") (pin "1") (pinfunction "1_1") (pintype "passive"))
      (node (ref "U4") (pin "44") (pinfunction "XTAL_N_44") (pintype "passive"))
      (node (ref "X1") (pin "3") (pinfunction "3_3") (pintype "passive"))
    )
    (net (code "59") (name "/XTAL_P") (class "Default")
      (node (ref "C24") (pin "1") (pinfunction "1_1") (pintype "passive"))
      (node (ref "U4") (pin "45") (pinfunction "XTAL_P_45") (pintype "passive"))
      (node (ref "X1") (pin "1") (pinfunction "1_1") (pintype "passive"))
    )
    (net (code "60") (name "GND") (class "Default")
      (node (ref "C10") (pin "1") (pinfunction "1_1") (pintype "passive"))
      (node (ref "C13") (pin "1") (pinfunction "1_1") (pintype "passive"))
      (node (ref "C14") (pin "1") (pinfunction "1_1") (pintype "passive"))
      (node (ref "C17") (pin "1") (pinfunction "1_1") (pintype "passive"))
      (node (ref "C2") (pin "1") (pinfunction "1_1") (pintype "passive"))
      (node (ref "C20") (pin "1") (pinfunction "1_1") (pintype "passive"))
      (node (ref "C21") (pin "1") (pinfunction "1_1") (pintype "passive"))
      (node (ref "C22") (pin "1") (pinfunction "1_1") (pintype "passive"))
      (node (ref "C24") (pin "2") (pinfunction "2_2") (pintype "passive"))
      (node (ref "C25") (pin "2") (pinfunction "2_2") (pintype "passive"))
      (node (ref "C26") (pin "1") (pinfunction "1_1") (pintype "passive"))
      (node (ref "C27") (pin "1") (pinfunction "1_1") (pintype "passive"))
      (node (ref "C28") (pin "1") (pinfunction "1_1") (pintype "passive"))
      (node (ref "C3") (pin "1") (pinfunction "1_1") (pintype "passive"))
      (node (ref "C4") (pin "1") (pinfunction "1_1") (pintype "passive"))
      (node (ref "C5") (pin "1") (pinfunction "1_1") (pintype "passive"))
      (node (ref "C6") (pin "1") (pinfunction "1_1") (pintype "passive"))
      (node (ref "C7") (pin "1") (pinfunction "1_1") (pintype "passive"))
      (node (ref "C8") (pin "1") (pinfunction "1_1") (pintype "passive"))
      (node (ref "C9") (pin "1") (pinfunction "1_1") (pintype "passive"))
      (node (ref "JP1") (pin "10") (pinfunction "10_10") (pintype "passive"))
      (node (ref "JP1") (pin "12") (pinfunction "12_12") (pintype "passive"))
      (node (ref "JP1") (pin "14") (pinfunction "14_14") (pintype "passive"))
      (node (ref "JP1") (pin "16") (pinfunction "16_16") (pintype "passive"))
      (node (ref "JP1") (pin "2") (pinfunction "2_2") (pintype "passive"))
      (node (ref "JP1") (pin "4") (pinfunction "4_4") (pintype "passive"))
      (node (ref "JP1") (pin "6") (pinfunction "6_6") (pintype "passive"))
      (node (ref "JP1") (pin "8") (pinfunction "8_8") (pintype "passive"))
      (node (ref "JP2") (pin "4") (pinfunction "4_4") (pintype "passive"))
      (node (ref "L2") (pin "1") (pinfunction "1_1") (pintype "passive"))
      (node (ref "R17") (pin "2") (pinfunction "2_2") (pintype "passive"))
      (node (ref "R22") (pin "2") (pinfunction "2_2") (pintype "passive"))
      (node (ref "R23") (pin "2") (pinfunction "2_2") (pintype "passive"))
      (node (ref "R31") (pin "2") (pinfunction "2_2") (pintype "passive"))
      (node (ref "R32") (pin "2") (pinfunction "2_2") (pintype "passive"))
      (node (ref "R44") (pin "2") (pinfunction "2_2") (pintype "passive"))
      (node (ref "R45") (pin "2") (pinfunction "2_2") (pintype "passive"))
      (node (ref "R5") (pin "2") (pinfunction "2_2") (pintype "passive"))
      (node (ref "SW1") (pin "2") (pinfunction "2_2") (pintype "passive"))
      (node (ref "SW2") (pin "2") (pinfunction "2_2") (pintype "passive"))
      (node (ref "TP13") (pin "1") (pinfunction "1_1") (pintype "passive"))
      (node (ref "U1") (pin "11") (pinfunction "V-_11") (pintype "passive"))
      (node (ref "U2") (pin "11") (pinfunction "V-_11") (pintype "passive"))
      (node (ref "U3") (pin "4") (pinfunction "GND_4") (pintype "passive"))
      (node (ref "U4") (pin "49") (pinfunction "GND_49") (pintype "passive"))
      (node (ref "U5") (pin "3") (pinfunction "GND_3") (pintype "passive"))
      (node (ref "X1") (pin "2") (pinfunction "2_2") (pintype "passive"))
      (node (ref "X1") (pin "4") (pinfunction "4_4") (pintype "passive"))
    )
    (net (code "61") (name "Net-(A1-ANT)") (class "Default")
      (node (ref "A1") (pin "1") (pinfunction "ANT_1") (pintype "passive"))
      (node (ref "C12") (pin "1") (pinfunction "1_1") (pintype "passive"))
      (node (ref "C14") (pin "2") (pinfunction "2_2") (pintype "passive"))
    )
    (net (code "62") (name "Net-(C12-Pad2)") (class "Default")
      (node (ref "C12") (pin "2") (pinfunction "2_2") (pintype "passive"))
      (node (ref "L2") (pin "2") (pinfunction "2_2") (pintype "passive"))
      (node (ref "R14") (pin "1") (pinfunction "1_1") (pintype "passive"))
    )
    (net (code "63") (name "Net-(JP1-Pad1)") (class "Default")
      (node (ref "JP1") (pin "1") (pinfunction "1_1") (pintype "passive"))
      (node (ref "R26") (pin "1") (pinfunction "1_1") (pintype "passive"))
    )
    (net (code "64") (name "Net-(JP1-Pad3)") (class "Default")
      (node (ref "JP1") (pin "3") (pinfunction "3_3") (pintype "passive"))
      (node (ref "R25") (pin "1") (pinfunction "1_1") (pintype "passive"))
    )
    (net (code "65") (name "Net-(JP1-Pad5)") (class "Default")
      (node (ref "JP1") (pin "5") (pinfunction "5_5") (pintype "passive"))
      (node (ref "R13") (pin "1") (pinfunction "1_1") (pintype "passive"))
    )
    (net (code "66") (name "Net-(JP1-Pad7)") (class "Default")
      (node (ref "JP1") (pin "7") (pinfunction "7_7") (pintype "passive"))
      (node (ref "R11") (pin "1") (pinfunction "1_1") (pintype "passive"))
    )
    (net (code "67") (name "Net-(JP1-Pad9)") (class "Default")
      (node (ref "JP1") (pin "9") (pinfunction "9_9") (pintype "passive"))
      (node (ref "R7") (pin "1") (pinfunction "1_1") (pintype "passive"))
    )
    (net (code "68") (name "Net-(JP1-Pad11)") (class "Default")
      (node (ref "JP1") (pin "11") (pinfunction "11_11") (pintype "passive"))
      (node (ref "R6") (pin "1") (pinfunction "1_1") (pintype "passive"))
    )
    (net (code "69") (name "Net-(JP1-Pad13)") (class "Default")
      (node (ref "JP1") (pin "13") (pinfunction "13_13") (pintype "passive"))
      (node (ref "R4") (pin "1") (pinfunction "1_1") (pintype "passive"))
    )
    (net (code "70") (name "Net-(JP1-Pad15)") (class "Default")
      (node (ref "JP1") (pin "15") (pinfunction "15_15") (pintype "passive"))
      (node (ref "R1") (pin "1") (pinfunction "1_1") (pintype "passive"))
    )
    (net (code "71") (name "Net-(LED1-K)") (class "Default")
      (node (ref "LED1") (pin "2") (pinfunction "K_2") (pintype "passive"))
      (node (ref "R37") (pin "2") (pinfunction "2_2") (pintype "passive"))
    )
    (net (code "72") (name "Net-(R2-Pad1)") (class "Default")
      (node (ref "R2") (pin "1") (pinfunction "1_1") (pintype "passive"))
      (node (ref "R3") (pin "2") (pinfunction "2_2") (pintype "passive"))
      (node (ref "R5") (pin "1") (pinfunction "1_1") (pintype "passive"))
    )
    (net (code "73") (name "Net-(R15-Pad1)") (class "Default")
      (node (ref "R15") (pin "1") (pinfunction "1_1") (pintype "passive"))
      (node (ref "R16") (pin "2") (pinfunction "2_2") (pintype "passive"))
      (node (ref "R17") (pin "1") (pinfunction "1_1") (pintype "passive"))
    )
    (net (code "74") (name "Net-(R18-Pad1)") (class "Default")
      (node (ref "R18") (pin "1") (pinfunction "1_1") (pintype "passive"))
      (node (ref "R19") (pin "2") (pinfunction "2_2") (pintype "passive"))
      (node (ref "R22") (pin "1") (pinfunction "1_1") (pintype "passive"))
    )
    (net (code "75") (name "Net-(R20-Pad1)") (class "Default")
      (node (ref "R20") (pin "1") (pinfunction "1_1") (pintype "passive"))
      (node (ref "R21") (pin "2") (pinfunction "2_2") (pintype "passive"))
      (node (ref "R23") (pin "1") (pinfunction "1_1") (pintype "passive"))
    )
    (net (code "76") (name "Net-(R27-Pad1)") (class "Default")
      (node (ref "R27") (pin "1") (pinfunction "1_1") (pintype "passive"))
      (node (ref "R28") (pin "2") (pinfunction "2_2") (pintype "passive"))
      (node (ref "R31") (pin "1") (pinfunction "1_1") (pintype "passive"))
    )
    (net (code "77") (name "Net-(R29-Pad1)") (class "Default")
      (node (ref "R29") (pin "1") (pinfunction "1_1") (pintype "passive"))
      (node (ref "R30") (pin "2") (pinfunction "2_2") (pintype "passive"))
      (node (ref "R32") (pin "1") (pinfunction "1_1") (pintype "passive"))
    )
    (net (code "78") (name "Net-(R35-Pad1)") (class "Default")
      (node (ref "R35") (pin "1") (pinfunction "1_1") (pintype "passive"))
      (node (ref "R36") (pin "2") (pinfunction "2_2") (pintype "passive"))
      (node (ref "R44") (pin "1") (pinfunction "1_1") (pintype "passive"))
    )
    (net (code "79") (name "Net-(R42-Pad1)") (class "Default")
      (node (ref "R42") (pin "1") (pinfunction "1_1") (pintype "passive"))
      (node (ref "R43") (pin "2") (pinfunction "2_2") (pintype "passive"))
      (node (ref "R45") (pin "1") (pinfunction "1_1") (pintype "passive"))
    )
    (net (code "80") (name "Net-(U4-LNA_IN)") (class "Default")
      (node (ref "R14") (pin "2") (pinfunction "2_2") (pintype "passive"))
      (node (ref "U4") (pin "2") (pinfunction "LNA_IN_2") (pintype "passive"))
    )
    (net (code "81") (name "Net-(U4-U0TXD)") (class "Default")
      (node (ref "R8") (pin "1") (pinfunction "1_1") (pintype "passive"))
      (node (ref "U4") (pin "41") (pinfunction "U0TXD_41") (pintype "passive"))
    )
    (net (code "82") (name "VDD_SDIO") (class "Default")
      (node (ref "C17") (pin "2") (pinfunction "2_2") (pintype "passive"))
      (node (ref "U3") (pin "8") (pinfunction "VCC_8") (pintype "passive"))
      (node (ref "U4") (pin "26") (pinfunction "VDD_SDIO_26") (pintype "passive"))
    )
    (net (code "83") (name "unconnected-(A1-GND-Pad2)") (class "Default")
      (node (ref "A1") (pin "2") (pinfunction "GND_2") (pintype "passive+no_connect"))
    )
  )
)
